# Adafruit_LM73100_Ideal_Diode_Breakout.net
KiCad netlist of a schematic drawn in EAGLE
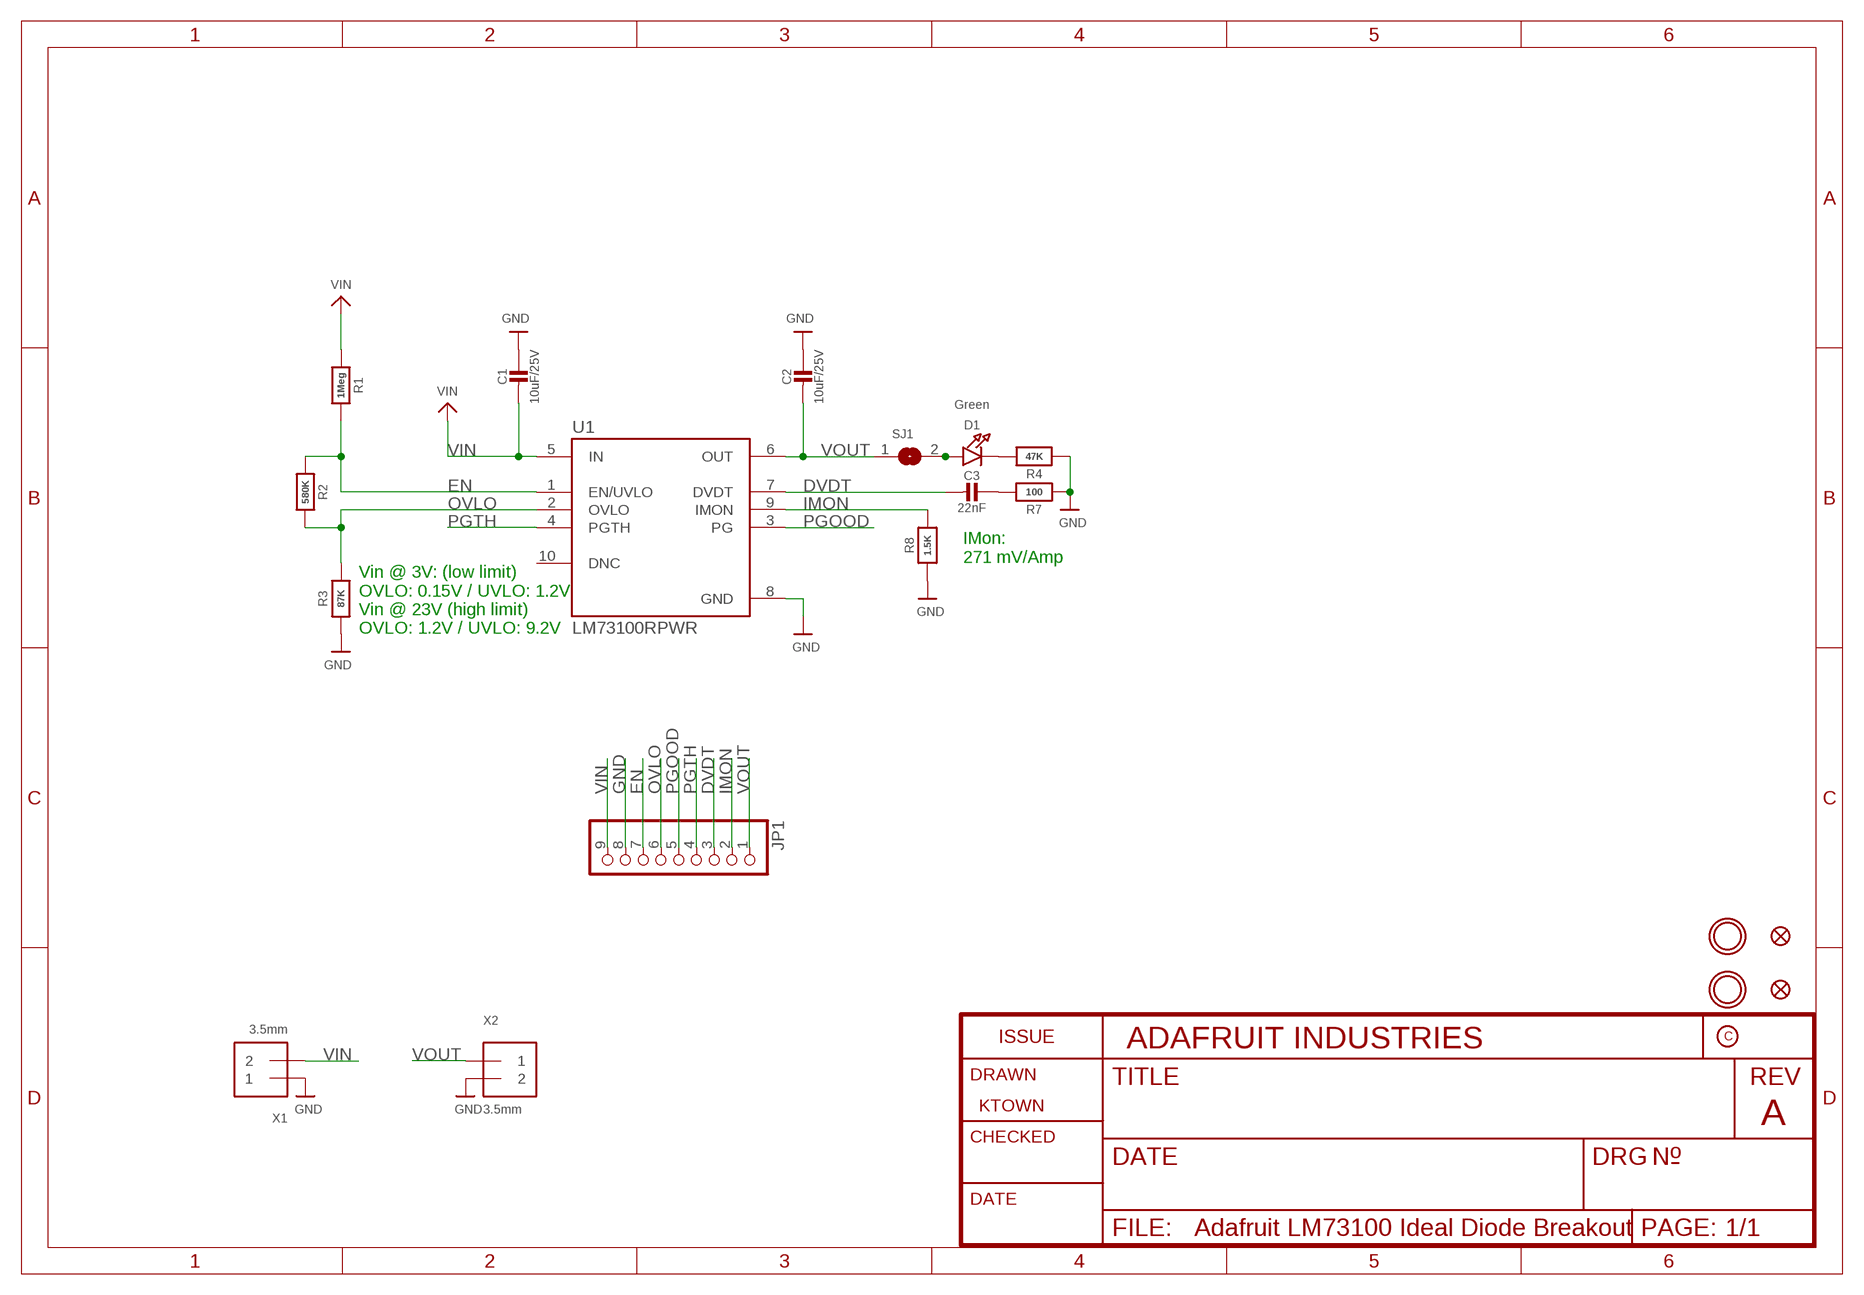
[diagram p0: schematic, sheet 1]

(export (version "E")
  (design (tool "Eeschema 10.0.6"))
  (components
    (comp (ref "C1")
      (value "10uF/25V")
      (footprint "eagle-import:0805-NO")
      (libsource (lib "eagle-import") (part "CAP_CERAMIC0805-NOOUTLINE"))
    )
    (comp (ref "C2")
      (value "10uF/25V")
      (footprint "eagle-import:0805-NO")
      (libsource (lib "eagle-import") (part "CAP_CERAMIC0805-NOOUTLINE"))
    )
    (comp (ref "C3")
      (value "22nF")
      (footprint "eagle-import:0603-NO")
      (libsource (lib "eagle-import") (part "CAP_CERAMIC0603_NO"))
    )
    (comp (ref "D1")
      (value "Green")
      (footprint "eagle-import:CHIPLED_0603_NOOUTLINE")
      (libsource (lib "eagle-import") (part "LED0603_NOOUTLINE"))
    )
    (comp (ref "FID1")
      (value "FIDUCIAL_0.5MM")
      (footprint "eagle-import:FIDUCIAL_0.5MM")
      (libsource (lib "eagle-import") (part "FIDUCIAL_0.5MM"))
    )
    (comp (ref "FID2")
      (value "FIDUCIAL_0.5MM")
      (footprint "eagle-import:FIDUCIAL_0.5MM")
      (libsource (lib "eagle-import") (part "FIDUCIAL_0.5MM"))
    )
    (comp (ref "JP1")
      (value "HEADER-1X970MIL")
      (footprint "eagle-import:1X09_ROUND_70")
      (libsource (lib "eagle-import") (part "HEADER-1X970MIL"))
    )
    (comp (ref "R1")
      (value "1Meg")
      (footprint "eagle-import:0603-NO")
      (libsource (lib "eagle-import") (part "RESISTOR_0603_NOOUT"))
    )
    (comp (ref "R2")
      (value "580K")
      (footprint "eagle-import:0603-NO")
      (libsource (lib "eagle-import") (part "RESISTOR_0603_NOOUT"))
    )
    (comp (ref "R3")
      (value "87K")
      (footprint "eagle-import:0603-NO")
      (libsource (lib "eagle-import") (part "RESISTOR_0603_NOOUT"))
    )
    (comp (ref "R4")
      (value "47K")
      (footprint "eagle-import:0603-NO")
      (libsource (lib "eagle-import") (part "RESISTOR_0603_NOOUT"))
    )
    (comp (ref "R7")
      (value "100")
      (footprint "eagle-import:0603-NO")
      (libsource (lib "eagle-import") (part "RESISTOR_0603_NOOUT"))
    )
    (comp (ref "R8")
      (value "1.5K")
      (footprint "eagle-import:_0402NO")
      (libsource (lib "eagle-import") (part "RESISTOR_0402NO"))
    )
    (comp (ref "SJ1")
      (value "SOLDERJUMPERCLOSED")
      (footprint "eagle-import:SOLDERJUMPER_CLOSEDWIRE")
      (libsource (lib "eagle-import") (part "SOLDERJUMPERCLOSED"))
    )
    (comp (ref "U$1")
      (value "MOUNTINGHOLE2.5")
      (footprint "eagle-import:MOUNTINGHOLE_2.5_PLATED")
      (libsource (lib "eagle-import") (part "MOUNTINGHOLE2.5"))
    )
    (comp (ref "U$9")
      (value "MOUNTINGHOLE2.5")
      (footprint "eagle-import:MOUNTINGHOLE_2.5_PLATED")
      (libsource (lib "eagle-import") (part "MOUNTINGHOLE2.5"))
    )
    (comp (ref "U1")
      (value "LM73100RPWR")
      (footprint "eagle-import:IC_LM73100RPWR")
      (fields (field (name "MANUFACTURER") "Texas Instruments"))
      (libsource (lib "eagle-import") (part "LM73100RPWR"))
    )
    (comp (ref "X1")
      (value "3.5mm")
      (footprint "eagle-import:TERMBLOCK_1X2-3.5MM")
      (fields (field (name "ROT") "0"))
      (libsource (lib "eagle-import") (part "TERMBLOCK_1X2_3.5MM"))
    )
    (comp (ref "X2")
      (value "3.5mm")
      (footprint "eagle-import:TERMBLOCK_1X2-3.5MM")
      (fields (field (name "ROT") "0"))
      (libsource (lib "eagle-import") (part "TERMBLOCK_1X2_3.5MM"))
    )
  )
  (nets
    (net (code "1") (name "/DVDT") (class "Default")
      (node (ref "C3") (pin "2") (pinfunction "2_2") (pintype "passive"))
      (node (ref "JP1") (pin "3") (pinfunction "3_3") (pintype "passive"))
      (node (ref "U1") (pin "7") (pinfunction "DVDT_7") (pintype "output"))
    )
    (net (code "2") (name "/EN") (class "Default")
      (node (ref "JP1") (pin "7") (pinfunction "7_7") (pintype "passive"))
      (node (ref "R1") (pin "1") (pinfunction "1_1") (pintype "passive"))
      (node (ref "R2") (pin "2") (pinfunction "2_2") (pintype "passive"))
      (node (ref "U1") (pin "1") (pinfunction "EN/UVLO_1") (pintype "input"))
    )
    (net (code "3") (name "/IMON") (class "Default")
      (node (ref "JP1") (pin "2") (pinfunction "2_2") (pintype "passive"))
      (node (ref "R8") (pin "2") (pinfunction "2_2") (pintype "passive"))
      (node (ref "U1") (pin "9") (pinfunction "IMON_9") (pintype "output"))
    )
    (net (code "4") (name "/OVLO") (class "Default")
      (node (ref "JP1") (pin "6") (pinfunction "6_6") (pintype "passive"))
      (node (ref "R2") (pin "1") (pinfunction "1_1") (pintype "passive"))
      (node (ref "R3") (pin "1") (pinfunction "1_1") (pintype "passive"))
      (node (ref "U1") (pin "2") (pinfunction "OVLO_2") (pintype "input"))
    )
    (net (code "5") (name "/PGOOD") (class "Default")
      (node (ref "JP1") (pin "5") (pinfunction "5_5") (pintype "passive"))
      (node (ref "U1") (pin "3") (pinfunction "PG_3") (pintype "output"))
    )
    (net (code "6") (name "/PGTH") (class "Default")
      (node (ref "JP1") (pin "4") (pinfunction "4_4") (pintype "passive"))
      (node (ref "U1") (pin "4") (pinfunction "PGTH_4") (pintype "input"))
    )
    (net (code "7") (name "/VOUT") (class "Default")
      (node (ref "C2") (pin "2") (pinfunction "2_2") (pintype "passive"))
      (node (ref "JP1") (pin "1") (pinfunction "1_1") (pintype "passive"))
      (node (ref "SJ1") (pin "1") (pinfunction "1_1") (pintype "passive"))
      (node (ref "U1") (pin "6") (pinfunction "OUT_6") (pintype "output"))
      (node (ref "X2") (pin "1") (pinfunction "1_1") (pintype "passive"))
    )
    (net (code "8") (name "GND") (class "Default")
      (node (ref "C1") (pin "1") (pinfunction "1_1") (pintype "passive"))
      (node (ref "C2") (pin "1") (pinfunction "1_1") (pintype "passive"))
      (node (ref "JP1") (pin "8") (pinfunction "8_8") (pintype "passive"))
      (node (ref "R3") (pin "2") (pinfunction "2_2") (pintype "passive"))
      (node (ref "R4") (pin "2") (pinfunction "2_2") (pintype "passive"))
      (node (ref "R7") (pin "1") (pinfunction "1_1") (pintype "passive"))
      (node (ref "R8") (pin "1") (pinfunction "1_1") (pintype "passive"))
      (node (ref "U1") (pin "8") (pinfunction "GND_8") (pintype "power_in"))
      (node (ref "X1") (pin "1") (pinfunction "1_1") (pintype "passive"))
      (node (ref "X2") (pin "2") (pinfunction "2_2") (pintype "passive"))
    )
    (net (code "9") (name "Net-(C3-Pad1)") (class "Default")
      (node (ref "C3") (pin "1") (pinfunction "1_1") (pintype "passive"))
      (node (ref "R7") (pin "2") (pinfunction "2_2") (pintype "passive"))
    )
    (net (code "10") (name "Net-(D1-PadA)") (class "Default")
      (node (ref "D1") (pin "A") (pinfunction "A_A") (pintype "passive"))
      (node (ref "SJ1") (pin "2") (pinfunction "2_2") (pintype "passive"))
    )
    (net (code "11") (name "Net-(D1-PadC)") (class "Default")
      (node (ref "D1") (pin "C") (pinfunction "C_C") (pintype "passive"))
      (node (ref "R4") (pin "1") (pinfunction "1_1") (pintype "passive"))
    )
    (net (code "12") (name "VIN") (class "Default")
      (node (ref "C1") (pin "2") (pinfunction "2_2") (pintype "passive"))
      (node (ref "JP1") (pin "9") (pinfunction "9_9") (pintype "passive"))
      (node (ref "R1") (pin "2") (pinfunction "2_2") (pintype "passive"))
      (node (ref "U1") (pin "5") (pinfunction "IN_5") (pintype "input"))
      (node (ref "X1") (pin "2") (pinfunction "2_2") (pintype "passive"))
    )
    (net (code "13") (name "unconnected-(U1-DNC-Pad10)") (class "Default")
      (node (ref "U1") (pin "10") (pinfunction "DNC_10") (pintype "no_connect"))
    )
  )
)
